# Battery_Circuit.net
KiCad netlist of a schematic drawn in Altium Designer
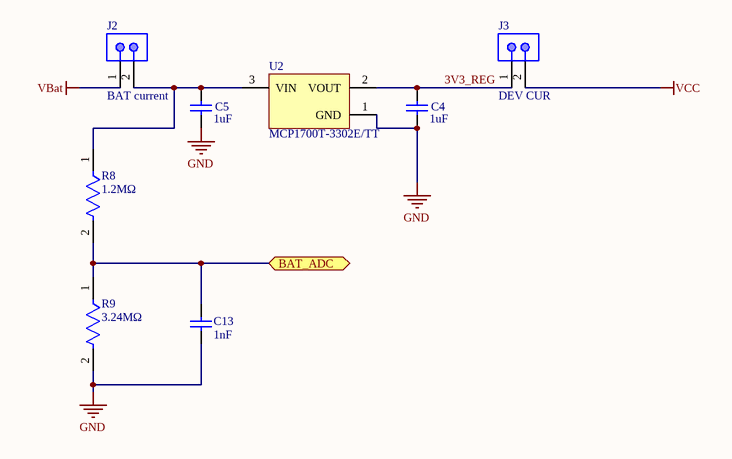
[diagram p0: Battery Circuit.SchDoc]

(export (version "E")
  (design (tool "Eeschema 10.0.6"))
  (components
    (comp (ref "C4")
      (value "1uF")
      (footprint "CAPC2013X145X50LL20T25")
      (fields (field (name "MANUFACTURER") "Kemet") (field (name "PART NUMBER") "C0805C105K4PACTU"))
      (libsource (lib "Altium Content Vault") (part "CAP"))
    )
    (comp (ref "C5")
      (value "1uF")
      (footprint "CAPC2013X145X50LL20T25")
      (fields (field (name "MANUFACTURER") "Kemet") (field (name "PART NUMBER") "C0805C105K4PACTU"))
      (libsource (lib "Altium Content Vault") (part "CAP"))
    )
    (comp (ref "C13")
      (value "1nF")
      (footprint "CAPC1005X55X25LL05T05")
      (fields (field (name "MANUFACTURER") "Vitramon") (field (name "PART NUMBER") "VJ0402Y102KXXCW1BC"))
      (libsource (lib "Altium Content Vault") (part "CAP"))
    )
    (comp (ref "J2")
      (value "BAT current")
      (footprint "TECO-5-146280-2_V")
      (fields (field (name "MANUFACTURER") "TE Connectivity"))
      (libsource (lib "Altium Content Vault") (part "CN-1P-M-R2"))
    )
    (comp (ref "J3")
      (value "DEV CUR")
      (footprint "TECO-5-146280-2_V")
      (fields (field (name "MANUFACTURER") "TE Connectivity"))
      (libsource (lib "Altium Content Vault") (part "CN-1P-M-R2"))
    )
    (comp (ref "R8")
      (value "1.2MΩ")
      (footprint "FP-CRCW0603-e3-IPC_A")
      (description "RES Thick Film, 1.2MΩ, 1%, 0.1W, 100ppm/°C, 0603")
      (fields (field (name "TOLERANCE") "1%"))
      (libsource (lib "Altium Content Vault") (part "1029c3af85768c4190bb7ad29bc67b5"))
    )
    (comp (ref "R9")
      (value "3.24MΩ")
      (footprint "FP-CRCW0603-e3-MFG")
      (description "RES Thick Film, 3.24MΩ, 1%, 0.1W, 100ppm/°C, 0603")
      (fields (field (name "TOLERANCE") "1%"))
      (libsource (lib "Altium Content Vault") (part "1029c3af85768c4190bb7ad29bc67b5"))
    )
    (comp (ref "U2")
      (value "MCP1700T-3302E/TT")
      (footprint "SOT-23-TT3_N")
      (description "Low Quiescent Current LDO, 3-Pin SOT-23, Extended Temperature, Tape and Reel")
      (libsource (lib "Altium Content Vault") (part "PM-LINEREG-MCP1700-IL3"))
    )
  )
  (nets
    (net (code "1") (name "/3V3_REG") (class "Default")
      (node (ref "C4") (pin "1") (pinfunction "1_1") (pintype "passive"))
      (node (ref "J3") (pin "1") (pinfunction "1_1") (pintype "passive"))
      (node (ref "U2") (pin "2") (pinfunction "VOUT_2") (pintype "power_in"))
    )
    (net (code "2") (name "/BAT_ADC") (class "Default")
      (node (ref "C13") (pin "2") (pinfunction "2_2") (pintype "passive"))
      (node (ref "R8") (pin "2") (pinfunction "2_2") (pintype "passive"))
      (node (ref "R9") (pin "1") (pinfunction "1_1") (pintype "passive"))
    )
    (net (code "3") (name "GND") (class "Default")
      (node (ref "C13") (pin "1") (pinfunction "1_1") (pintype "passive"))
      (node (ref "C4") (pin "2") (pinfunction "2_2") (pintype "passive"))
      (node (ref "C5") (pin "2") (pinfunction "2_2") (pintype "passive"))
      (node (ref "R9") (pin "2") (pinfunction "2_2") (pintype "passive"))
      (node (ref "U2") (pin "1") (pinfunction "GND_1") (pintype "power_in"))
    )
    (net (code "4") (name "Net-(U2-VIN)") (class "Default")
      (node (ref "C5") (pin "1") (pinfunction "1_1") (pintype "passive"))
      (node (ref "J2") (pin "2") (pinfunction "2_2") (pintype "passive"))
      (node (ref "R8") (pin "1") (pinfunction "1_1") (pintype "passive"))
      (node (ref "U2") (pin "3") (pinfunction "VIN_3") (pintype "power_in"))
    )
    (net (code "5") (name "VBat") (class "Default")
      (node (ref "J2") (pin "1") (pinfunction "1_1") (pintype "passive"))
    )
    (net (code "6") (name "VCC") (class "Default")
      (node (ref "J3") (pin "2") (pinfunction "2_2") (pintype "passive"))
    )
  )
)
